# Power_Supply.net
KiCad netlist of a schematic drawn in Altium Designer
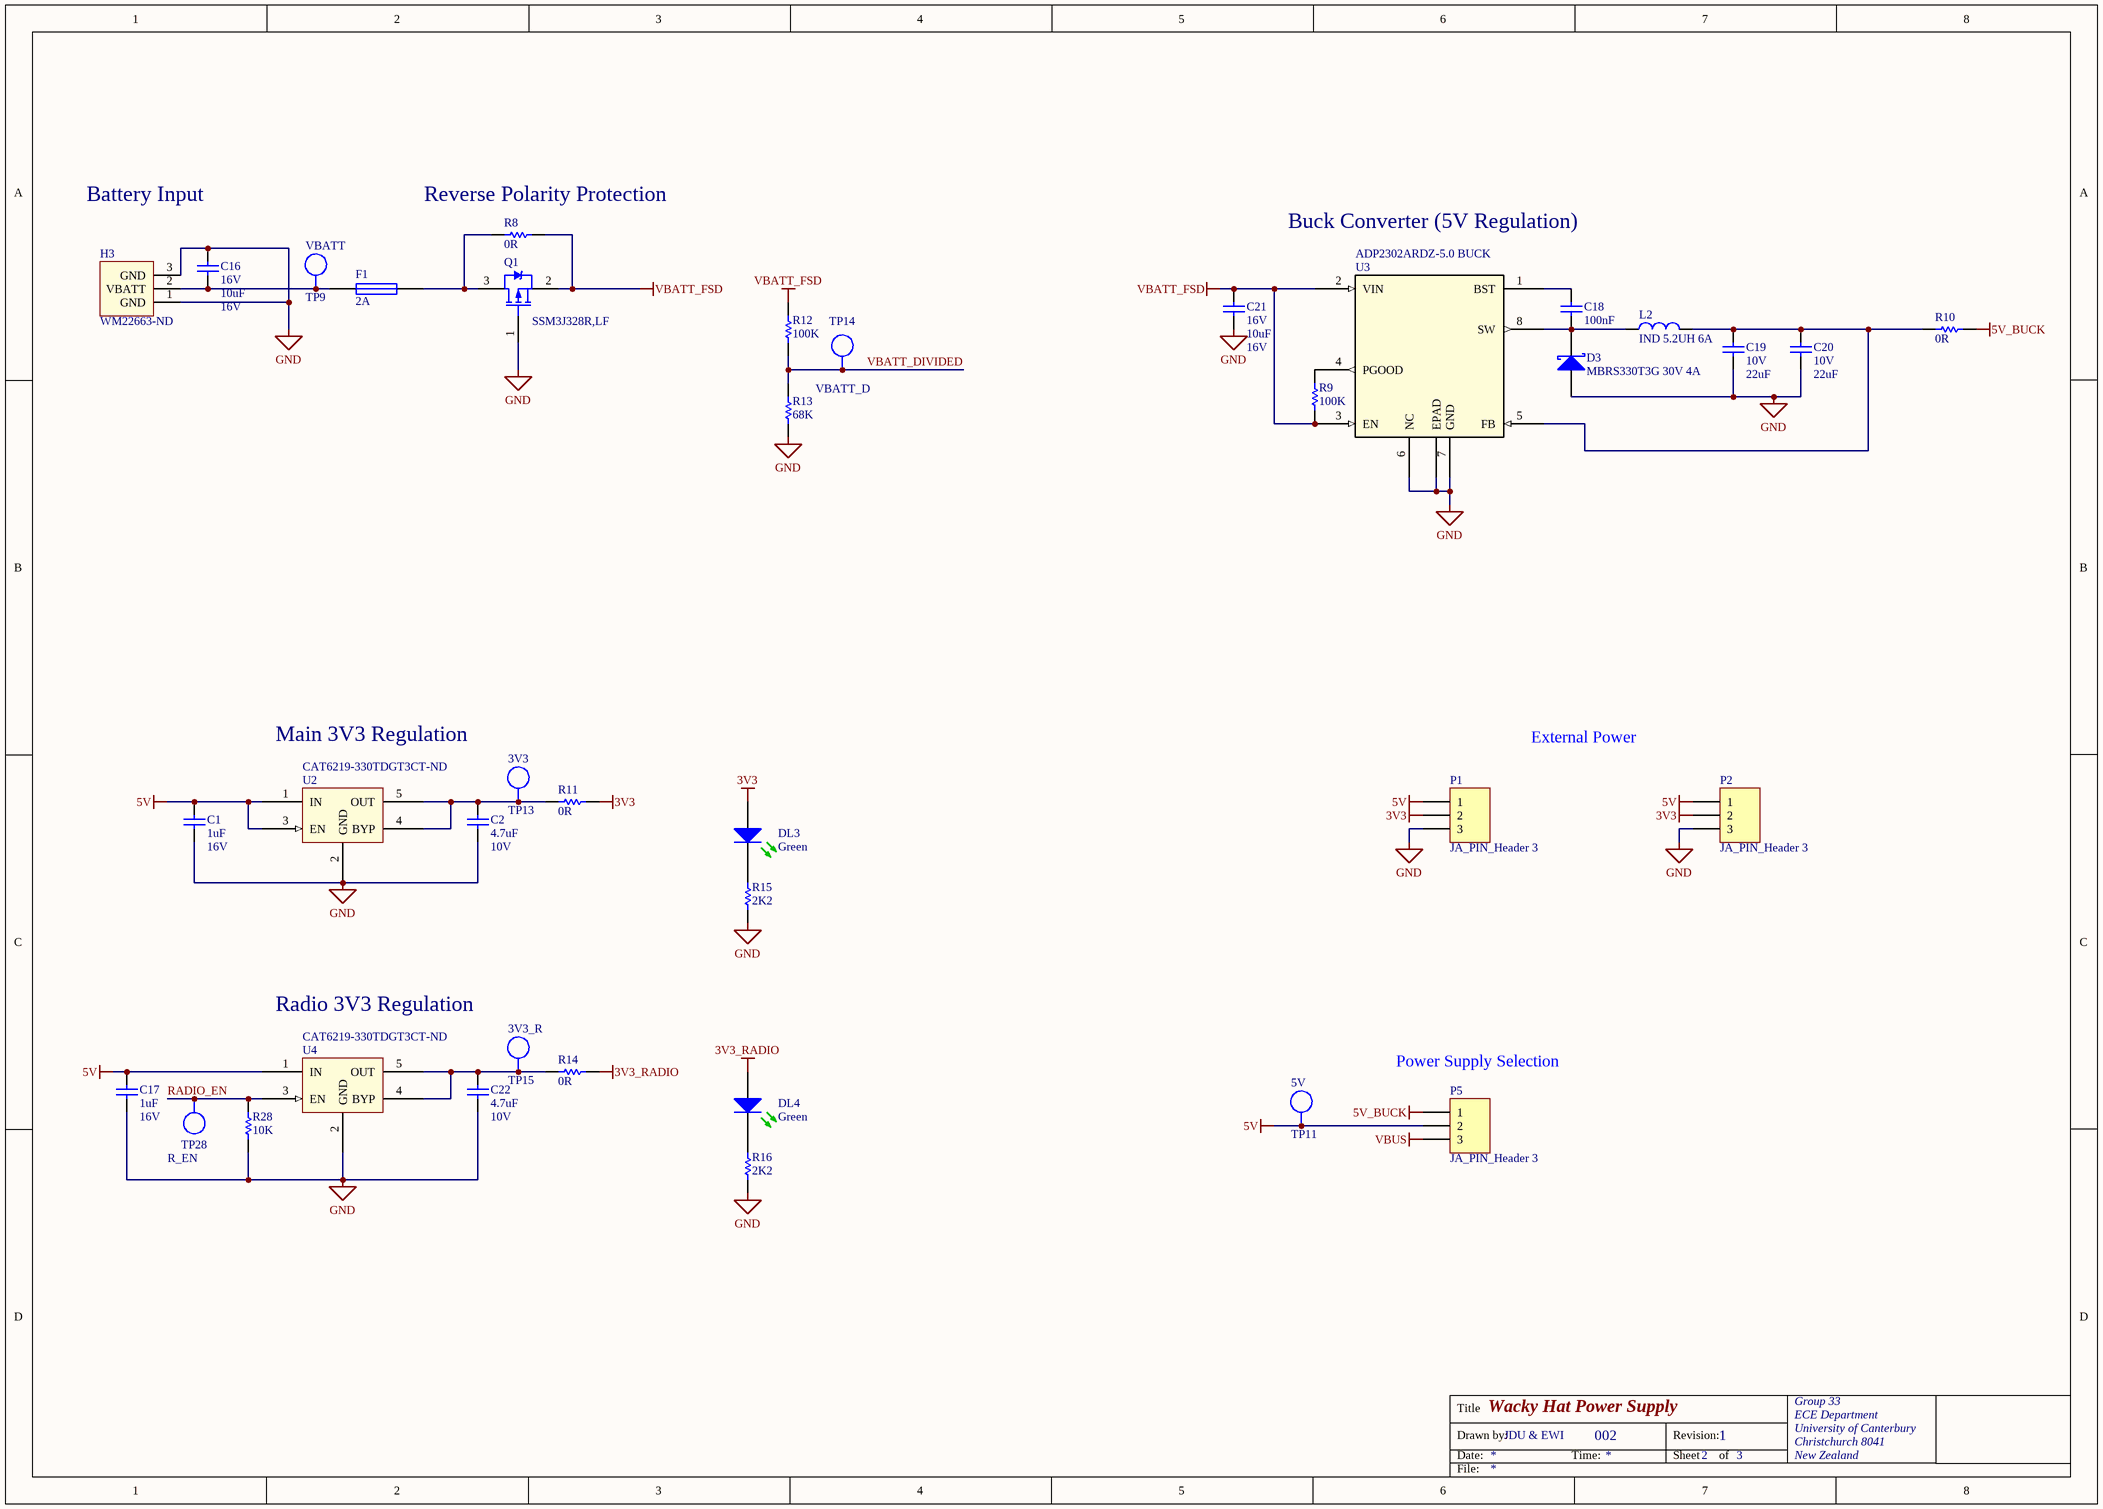
[diagram p0: Power_Supply.SchDoc]

(export (version "E")
  (design (tool "Eeschema 10.0.6"))
  (components
    (comp (ref "C1")
      (value "1uF")
      (footprint "CAPC1608L")
      (description "CAP CER 1uF Y5V -20% +80% 16V 0603")
      (fields (field (name "MAX VOLTAGE") "16V"))
      (libsource (lib "ECE_ComponentsAD23") (part "CC_1uF_0603"))
    )
    (comp (ref "C2")
      (value "4.7uF")
      (footprint "CAPC1608N")
      (description "CAP CER 4.7uF X5R +-20%  10V 0603")
      (fields (field (name "MAX VOLTAGE") "10V"))
      (libsource (lib "ECE_ComponentsAD23") (part "CC_4.7uF_0603"))
    )
    (comp (ref "C16")
      (value "10uF")
      (footprint "CAPC2012L")
      (description "CAP CER 10uF X5R 16V 0805")
      (fields
        (field (name "MANUFACTURER") "Samsung Electro-Mechanics")
        (field (name "MANUFACTURER PART NUMBER") "CL21A106KOQNNWE")
        (field (name "VOLTAGE - RATED") "16V")
        (field (name "MAX VOLTAGE") "16V")
      )
      (libsource (lib "ECE_ComponentsAD23") (part "CC_10uF_0805_16V"))
    )
    (comp (ref "C17")
      (value "1uF")
      (footprint "CAPC1608L")
      (description "CAP CER 1uF Y5V -20% +80% 16V 0603")
      (fields (field (name "MAX VOLTAGE") "16V"))
      (libsource (lib "ECE_ComponentsAD23") (part "CC_1uF_0603"))
    )
    (comp (ref "C18")
      (value "100nF")
      (footprint "CAPC1608L")
      (description "CAP CER 100nF X7R +-10% 50V 0603")
      (libsource (lib "ECE_ComponentsAD23") (part "CC_100nF_0603"))
    )
    (comp (ref "C19")
      (value "22uF")
      (footprint "CAPC3216L")
      (description "CAP CER 22uF Y5V -20% +80% 10V 1206")
      (fields (field (name "MAX VOLTAGE") "10V"))
      (libsource (lib "ECE_ComponentsAD23") (part "CC_22uF_1206"))
    )
    (comp (ref "C20")
      (value "22uF")
      (footprint "CAPC3216L")
      (description "CAP CER 22uF Y5V -20% +80% 10V 1206")
      (fields (field (name "MAX VOLTAGE") "10V"))
      (libsource (lib "ECE_ComponentsAD23") (part "CC_22uF_1206"))
    )
    (comp (ref "C21")
      (value "10uF")
      (footprint "CAPC2012L")
      (description "CAP CER 10uF X5R 16V 0805")
      (fields
        (field (name "MANUFACTURER") "Samsung Electro-Mechanics")
        (field (name "MANUFACTURER PART NUMBER") "CL21A106KOQNNWE")
        (field (name "VOLTAGE - RATED") "16V")
        (field (name "MAX VOLTAGE") "16V")
      )
      (libsource (lib "ECE_ComponentsAD23") (part "CC_10uF_0805_16V"))
    )
    (comp (ref "C22")
      (value "4.7uF")
      (footprint "CAPC1608N")
      (description "CAP CER 4.7uF X5R +-20%  10V 0603")
      (fields (field (name "MAX VOLTAGE") "10V"))
      (libsource (lib "ECE_ComponentsAD23") (part "CC_4.7uF_0603"))
    )
    (comp (ref "D3")
      (value "MBRS330T3G 30V 4A")
      (footprint "SMC")
      (description "SCHOTTKY  30V 4A")
      (fields
        (field (name "MANUFACTURER") "ON Semiconductor")
        (field (name "MANUFACTURER PART NUMBER") "MBRS330T3G")
      )
      (libsource (lib "ENCE461AD23") (part "MBRS330T3G"))
    )
    (comp (ref "DL3")
      (value "Green")
      (footprint "WL-SMCW0603")
      (description "LED Green 430mcd 0603 SMD")
      (fields
        (field (name "MANUFACTURER") "WURTH ELEKTRONIK")
        (field (name "MANUFACTURER PART NUMBER") "150060GS75000")
        (field (name "LED COLOUR") "Green")
      )
      (libsource (lib "ECE_ComponentsAD23") (part "DL_150060GS75000"))
    )
    (comp (ref "DL4")
      (value "Green")
      (footprint "WL-SMCW0603")
      (description "LED Green 430mcd 0603 SMD")
      (fields
        (field (name "MANUFACTURER") "WURTH ELEKTRONIK")
        (field (name "MANUFACTURER PART NUMBER") "150060GS75000")
        (field (name "LED COLOUR") "Green")
      )
      (libsource (lib "ECE_ComponentsAD23") (part "DL_150060GS75000"))
    )
    (comp (ref "F1")
      (value "2A")
      (footprint "RESC3216N")
      (description "Fuse 2.0A Very Fast Acting 1206 SMD")
      (fields
        (field (name "MANUFACTURER") "MULTICOMP")
        (field (name "MANUFACTURER PART NUMBER") "MC12CF 002")
      )
      (libsource (lib "ECE_ComponentsAD23") (part "FS_Fuse_2.0A"))
    )
    (comp (ref "H3")
      (value "Battery_HEADER_3pin")
      (footprint "BATT_HEADER_3POS")
      (description "3Pin Header 2.54mm spacing\r\nDigikey #WM22663-ND")
      (fields (field (name "SUPPLIER PART NUMBER 1") "WM22663-ND"))
      (libsource (lib "ENCE461AD23") (part "Battery_HEADER_3pin"))
    )
    (comp (ref "L2")
      (value "IND 5.2UH 6A")
      (footprint "INDUCTOR5u2")
      (description "FIXED IND 5.2UH 6A 22 MOHM SMD")
      (fields
        (field (name "MANUFACTURER") "Sumida America Components Inc.")
        (field (name "MANUFACTURER PART NUMBER") "CDRH104RNP-5R2NC")
      )
      (libsource (lib "ENCE461AD23") (part "CDRH104RNP-5R2NC"))
    )
    (comp (ref "P1")
      (value "JA_PIN_Header 3")
      (footprint "HDR1X3")
      (description "Header, 3-Pin")
      (fields (field (name "PUBLISHER") "Altium Limited"))
      (libsource (lib "ECE_ComponentsAD23") (part "JA_PIN_Header 3"))
    )
    (comp (ref "P2")
      (value "JA_PIN_Header 3")
      (footprint "HDR1X3")
      (description "Header, 3-Pin")
      (fields (field (name "PUBLISHER") "Altium Limited"))
      (libsource (lib "ECE_ComponentsAD23") (part "JA_PIN_Header 3"))
    )
    (comp (ref "P5")
      (value "JA_PIN_Header 3")
      (footprint "HDR1X3")
      (description "Header, 3-Pin")
      (fields (field (name "PUBLISHER") "Altium Limited"))
      (libsource (lib "ECE_ComponentsAD23") (part "JA_PIN_Header 3"))
    )
    (comp (ref "Q1")
      (value "SSM3J328R,LF")
      (footprint "SOT23_L")
      (description "MOSFET P-CH 20V 6A SOT23-3")
      (fields
        (field (name "MANUFACTURER") "Toshiba")
        (field (name "MANUFACTURER PART NUMBER") "SSM3J328R,LF")
      )
      (libsource (lib "ECE_ComponentsAD23") (part "TM_SSM3J328R"))
    )
    (comp (ref "R8")
      (value "0R")
      (footprint "RESC1608L")
      (description "RES 0.0 OHM 1/10W 5% 0603 SMD")
      (libsource (lib "ECE_ComponentsAD23") (part "RS_0R0"))
    )
    (comp (ref "R9")
      (value "100K")
      (footprint "RESC1608L")
      (description "RES 100K OHM 1/10W 5% 0603 SMD")
      (libsource (lib "ECE_ComponentsAD23") (part "RS_100K"))
    )
    (comp (ref "R10")
      (value "0R")
      (footprint "RESC1608L")
      (description "RES 0.0 OHM 1/10W 5% 0603 SMD")
      (libsource (lib "ECE_ComponentsAD23") (part "RS_0R0"))
    )
    (comp (ref "R11")
      (value "0R")
      (footprint "RESC1608L")
      (description "RES 0.0 OHM 1/10W 5% 0603 SMD")
      (libsource (lib "ECE_ComponentsAD23") (part "RS_0R0"))
    )
    (comp (ref "R12")
      (value "100K")
      (footprint "RESC1608L")
      (description "RES 100K OHM 1/10W 5% 0603 SMD")
      (libsource (lib "ECE_ComponentsAD23") (part "RS_100K"))
    )
    (comp (ref "R13")
      (value "68K")
      (footprint "RESC1608L")
      (description "RES 68.0K OHM 1/10W 5% 0603 SMD")
      (libsource (lib "ECE_ComponentsAD23") (part "RS_68K"))
    )
    (comp (ref "R14")
      (value "0R")
      (footprint "RESC1608L")
      (description "RES 0.0 OHM 1/10W 5% 0603 SMD")
      (libsource (lib "ECE_ComponentsAD23") (part "RS_0R0"))
    )
    (comp (ref "R15")
      (value "2K2")
      (footprint "RESC1608L")
      (description "RES 2.2K OHM 1/10W 5% 0603 SMD")
      (libsource (lib "ECE_ComponentsAD23") (part "RS_2K2"))
    )
    (comp (ref "R16")
      (value "2K2")
      (footprint "RESC1608L")
      (description "RES 2.2K OHM 1/10W 5% 0603 SMD")
      (libsource (lib "ECE_ComponentsAD23") (part "RS_2K2"))
    )
    (comp (ref "R28")
      (value "10K")
      (footprint "RESC1608L")
      (description "RES 10.0K OHM 1/10W 5% 0603 SMD")
      (libsource (lib "ECE_ComponentsAD23") (part "RS_10K"))
    )
    (comp (ref "TP9")
      (value "VBATT")
      (footprint "TP_1206")
      (description "Test-Point 3.3x1.6x2.1mm SMD")
      (fields
        (field (name "MANUFACTURER") "Harwin Inc")
        (field (name "MANUFACTURER PART NUMBER") "S1751-46R")
      )
      (libsource (lib "ECE_ComponentsAD23") (part "TP_1206"))
    )
    (comp (ref "TP11")
      (value "5V")
      (footprint "TP_1206")
      (description "Test-Point 3.3x1.6x2.1mm SMD")
      (fields
        (field (name "MANUFACTURER") "Harwin Inc")
        (field (name "MANUFACTURER PART NUMBER") "S1751-46R")
      )
      (libsource (lib "ECE_ComponentsAD23") (part "TP_1206"))
    )
    (comp (ref "TP13")
      (value "3V3")
      (footprint "TP_1206")
      (description "Test-Point 3.3x1.6x2.1mm SMD")
      (fields
        (field (name "MANUFACTURER") "Harwin Inc")
        (field (name "MANUFACTURER PART NUMBER") "S1751-46R")
      )
      (libsource (lib "ECE_ComponentsAD23") (part "TP_1206"))
    )
    (comp (ref "TP14")
      (value "VBATT_D")
      (footprint "TP_1206")
      (description "Test-Point 3.3x1.6x2.1mm SMD")
      (fields
        (field (name "MANUFACTURER") "Harwin Inc")
        (field (name "MANUFACTURER PART NUMBER") "S1751-46R")
      )
      (libsource (lib "ECE_ComponentsAD23") (part "TP_1206"))
    )
    (comp (ref "TP15")
      (value "3V3_R")
      (footprint "TP_1206")
      (description "Test-Point 3.3x1.6x2.1mm SMD")
      (fields
        (field (name "MANUFACTURER") "Harwin Inc")
        (field (name "MANUFACTURER PART NUMBER") "S1751-46R")
      )
      (libsource (lib "ECE_ComponentsAD23") (part "TP_1206"))
    )
    (comp (ref "TP28")
      (value "R_EN")
      (footprint "TP_1206")
      (description "Test-Point 3.3x1.6x2.1mm SMD")
      (fields
        (field (name "MANUFACTURER") "Harwin Inc")
        (field (name "MANUFACTURER PART NUMBER") "S1751-46R")
      )
      (libsource (lib "ECE_ComponentsAD23") (part "TP_1206"))
    )
    (comp (ref "U2")
      (value "CAT6219-330TDGT3")
      (footprint "SOT95P280X145-5N")
      (description "IC REG LIN 3.3V 500MA TSOT23-5")
      (fields
        (field (name "BASE PART NUMBER") "CAT6219")
        (field (name "SUPPLIER PART NUMBER") "CAT6219-330TDGT3CT-ND")
      )
      (libsource (lib "ENCE461AD23") (part "SV_CAT6219-330TDGT3"))
    )
    (comp (ref "U3")
      (value "ADP2302ARDZ-5.0 BUCK")
      (footprint "RD_8_1")
      (description "IC REG BUCK 5V 2A 8SOIC")
      (fields (field (name "MANUFACTURER_PART_NUMBER") "ADP2302ARDZ-5.0-R7"))
      (libsource (lib "ENCE461AD23") (part "ADP2302ARDZ-5.0-R7"))
    )
    (comp (ref "U4")
      (value "CAT6219-330TDGT3")
      (footprint "SOT95P280X145-5N")
      (description "IC REG LIN 3.3V 500MA TSOT23-5")
      (fields
        (field (name "BASE PART NUMBER") "CAT6219")
        (field (name "SUPPLIER PART NUMBER") "CAT6219-330TDGT3CT-ND")
      )
      (libsource (lib "ENCE461AD23") (part "SV_CAT6219-330TDGT3"))
    )
  )
  (nets
    (net (code "1") (name "/RADIO_EN") (class "Default")
      (node (ref "R28") (pin "2") (pinfunction "2_2") (pintype "passive"))
      (node (ref "TP28") (pin "1") (pinfunction "1_1") (pintype "passive"))
      (node (ref "U4") (pin "3") (pinfunction "EN_3") (pintype "input"))
    )
    (net (code "2") (name "/VBATT_DIVIDED") (class "Default")
      (node (ref "R12") (pin "1") (pinfunction "1_1") (pintype "passive"))
      (node (ref "R13") (pin "2") (pinfunction "2_2") (pintype "passive"))
      (node (ref "TP14") (pin "1") (pinfunction "1_1") (pintype "passive"))
    )
    (net (code "3") (name "3V3") (class "Default")
      (node (ref "DL3") (pin "2") (pinfunction "A_2") (pintype "passive"))
      (node (ref "P1") (pin "2") (pinfunction "2_2") (pintype "passive"))
      (node (ref "P2") (pin "2") (pinfunction "2_2") (pintype "passive"))
      (node (ref "R11") (pin "2") (pinfunction "2_2") (pintype "passive"))
    )
    (net (code "4") (name "3V3_RADIO") (class "Default")
      (node (ref "DL4") (pin "2") (pinfunction "A_2") (pintype "passive"))
      (node (ref "R14") (pin "2") (pinfunction "2_2") (pintype "passive"))
    )
    (net (code "5") (name "5V") (class "Default")
      (node (ref "C1") (pin "1") (pinfunction "1_1") (pintype "passive"))
      (node (ref "C17") (pin "1") (pinfunction "1_1") (pintype "passive"))
      (node (ref "P1") (pin "1") (pinfunction "1_1") (pintype "passive"))
      (node (ref "P2") (pin "1") (pinfunction "1_1") (pintype "passive"))
      (node (ref "P5") (pin "2") (pinfunction "2_2") (pintype "passive"))
      (node (ref "TP11") (pin "1") (pinfunction "1_1") (pintype "passive"))
      (node (ref "U2") (pin "1") (pinfunction "IN_1") (pintype "power_in"))
      (node (ref "U2") (pin "3") (pinfunction "EN_3") (pintype "input"))
      (node (ref "U4") (pin "1") (pinfunction "IN_1") (pintype "power_in"))
    )
    (net (code "6") (name "5V_BUCK") (class "Default")
      (node (ref "P5") (pin "1") (pinfunction "1_1") (pintype "passive"))
      (node (ref "R10") (pin "2") (pinfunction "2_2") (pintype "passive"))
    )
    (net (code "7") (name "GND") (class "Default")
      (node (ref "C1") (pin "2") (pinfunction "2_2") (pintype "passive"))
      (node (ref "C16") (pin "2") (pinfunction "2_2") (pintype "passive"))
      (node (ref "C17") (pin "2") (pinfunction "2_2") (pintype "passive"))
      (node (ref "C19") (pin "1") (pinfunction "1_1") (pintype "passive"))
      (node (ref "C2") (pin "1") (pinfunction "1_1") (pintype "passive"))
      (node (ref "C20") (pin "1") (pinfunction "1_1") (pintype "passive"))
      (node (ref "C21") (pin "1") (pinfunction "1_1") (pintype "passive"))
      (node (ref "C22") (pin "1") (pinfunction "1_1") (pintype "passive"))
      (node (ref "D3") (pin "1") (pinfunction "A_1") (pintype "passive"))
      (node (ref "H3") (pin "1") (pinfunction "GND_1") (pintype "passive"))
      (node (ref "H3") (pin "3") (pinfunction "GND_3") (pintype "passive"))
      (node (ref "P1") (pin "3") (pinfunction "3_3") (pintype "passive"))
      (node (ref "P2") (pin "3") (pinfunction "3_3") (pintype "passive"))
      (node (ref "Q1") (pin "1") (pinfunction "1_1") (pintype "passive"))
      (node (ref "R13") (pin "1") (pinfunction "1_1") (pintype "passive"))
      (node (ref "R15") (pin "1") (pinfunction "1_1") (pintype "passive"))
      (node (ref "R16") (pin "1") (pinfunction "1_1") (pintype "passive"))
      (node (ref "R28") (pin "1") (pinfunction "1_1") (pintype "passive"))
      (node (ref "U2") (pin "2") (pinfunction "GND_2") (pintype "power_in"))
      (node (ref "U3") (pin "6") (pinfunction "NC_6") (pintype "passive"))
      (node (ref "U3") (pin "7") (pinfunction "GND_7") (pintype "power_in"))
      (node (ref "U3") (pin "EPAD") (pinfunction "EPAD_EPAD") (pintype "passive"))
      (node (ref "U4") (pin "2") (pinfunction "GND_2") (pintype "power_in"))
    )
    (net (code "8") (name "Net-(D3-K)") (class "Default")
      (node (ref "C18") (pin "1") (pinfunction "1_1") (pintype "passive"))
      (node (ref "D3") (pin "2") (pinfunction "K_2") (pintype "passive"))
      (node (ref "L2") (pin "1") (pintype "passive"))
      (node (ref "U3") (pin "8") (pinfunction "SW_8") (pintype "output"))
    )
    (net (code "9") (name "Net-(DL3-K)") (class "Default")
      (node (ref "DL3") (pin "1") (pinfunction "K_1") (pintype "passive"))
      (node (ref "R15") (pin "2") (pinfunction "2_2") (pintype "passive"))
    )
    (net (code "10") (name "Net-(DL4-K)") (class "Default")
      (node (ref "DL4") (pin "1") (pinfunction "K_1") (pintype "passive"))
      (node (ref "R16") (pin "2") (pinfunction "2_2") (pintype "passive"))
    )
    (net (code "11") (name "Net-(F1-Pad2)") (class "Default")
      (node (ref "F1") (pin "2") (pinfunction "2_2") (pintype "passive"))
      (node (ref "Q1") (pin "3") (pinfunction "3_3") (pintype "passive"))
      (node (ref "R8") (pin "1") (pinfunction "1_1") (pintype "passive"))
    )
    (net (code "12") (name "Net-(H3-VBATT)") (class "Default")
      (node (ref "C16") (pin "1") (pinfunction "1_1") (pintype "passive"))
      (node (ref "F1") (pin "1") (pinfunction "1_1") (pintype "passive"))
      (node (ref "H3") (pin "2") (pinfunction "VBATT_2") (pintype "passive"))
      (node (ref "TP9") (pin "1") (pinfunction "1_1") (pintype "passive"))
    )
    (net (code "13") (name "Net-(U2-BYP)") (class "Default")
      (node (ref "C2") (pin "2") (pinfunction "2_2") (pintype "passive"))
      (node (ref "R11") (pin "1") (pinfunction "1_1") (pintype "passive"))
      (node (ref "TP13") (pin "1") (pinfunction "1_1") (pintype "passive"))
      (node (ref "U2") (pin "4") (pinfunction "BYP_4") (pintype "passive"))
      (node (ref "U2") (pin "5") (pinfunction "OUT_5") (pintype "power_in"))
    )
    (net (code "14") (name "Net-(U3-BST)") (class "Default")
      (node (ref "C18") (pin "2") (pinfunction "2_2") (pintype "passive"))
      (node (ref "U3") (pin "1") (pinfunction "BST_1") (pintype "passive"))
    )
    (net (code "15") (name "Net-(U3-FB)") (class "Default")
      (node (ref "C19") (pin "2") (pinfunction "2_2") (pintype "passive"))
      (node (ref "C20") (pin "2") (pinfunction "2_2") (pintype "passive"))
      (node (ref "L2") (pin "2") (pintype "passive"))
      (node (ref "R10") (pin "1") (pinfunction "1_1") (pintype "passive"))
      (node (ref "U3") (pin "5") (pinfunction "FB_5") (pintype "input"))
    )
    (net (code "16") (name "Net-(U3-PGOOD)") (class "Default")
      (node (ref "R9") (pin "2") (pinfunction "2_2") (pintype "passive"))
      (node (ref "U3") (pin "4") (pinfunction "PGOOD_4") (pintype "output"))
    )
    (net (code "17") (name "Net-(U4-BYP)") (class "Default")
      (node (ref "C22") (pin "2") (pinfunction "2_2") (pintype "passive"))
      (node (ref "R14") (pin "1") (pinfunction "1_1") (pintype "passive"))
      (node (ref "TP15") (pin "1") (pinfunction "1_1") (pintype "passive"))
      (node (ref "U4") (pin "4") (pinfunction "BYP_4") (pintype "passive"))
      (node (ref "U4") (pin "5") (pinfunction "OUT_5") (pintype "power_in"))
    )
    (net (code "18") (name "VBATT_FSD") (class "Default")
      (node (ref "C21") (pin "2") (pinfunction "2_2") (pintype "passive"))
      (node (ref "Q1") (pin "2") (pinfunction "2_2") (pintype "passive"))
      (node (ref "R12") (pin "2") (pinfunction "2_2") (pintype "passive"))
      (node (ref "R8") (pin "2") (pinfunction "2_2") (pintype "passive"))
      (node (ref "R9") (pin "1") (pinfunction "1_1") (pintype "passive"))
      (node (ref "U3") (pin "2") (pinfunction "VIN_2") (pintype "input"))
      (node (ref "U3") (pin "3") (pinfunction "EN_3") (pintype "input"))
    )
    (net (code "19") (name "VBUS") (class "Default")
      (node (ref "P5") (pin "3") (pinfunction "3_3") (pintype "passive"))
    )
  )
)
